# MCU_ESP32.net
KiCad netlist of a schematic drawn in Altium Designer
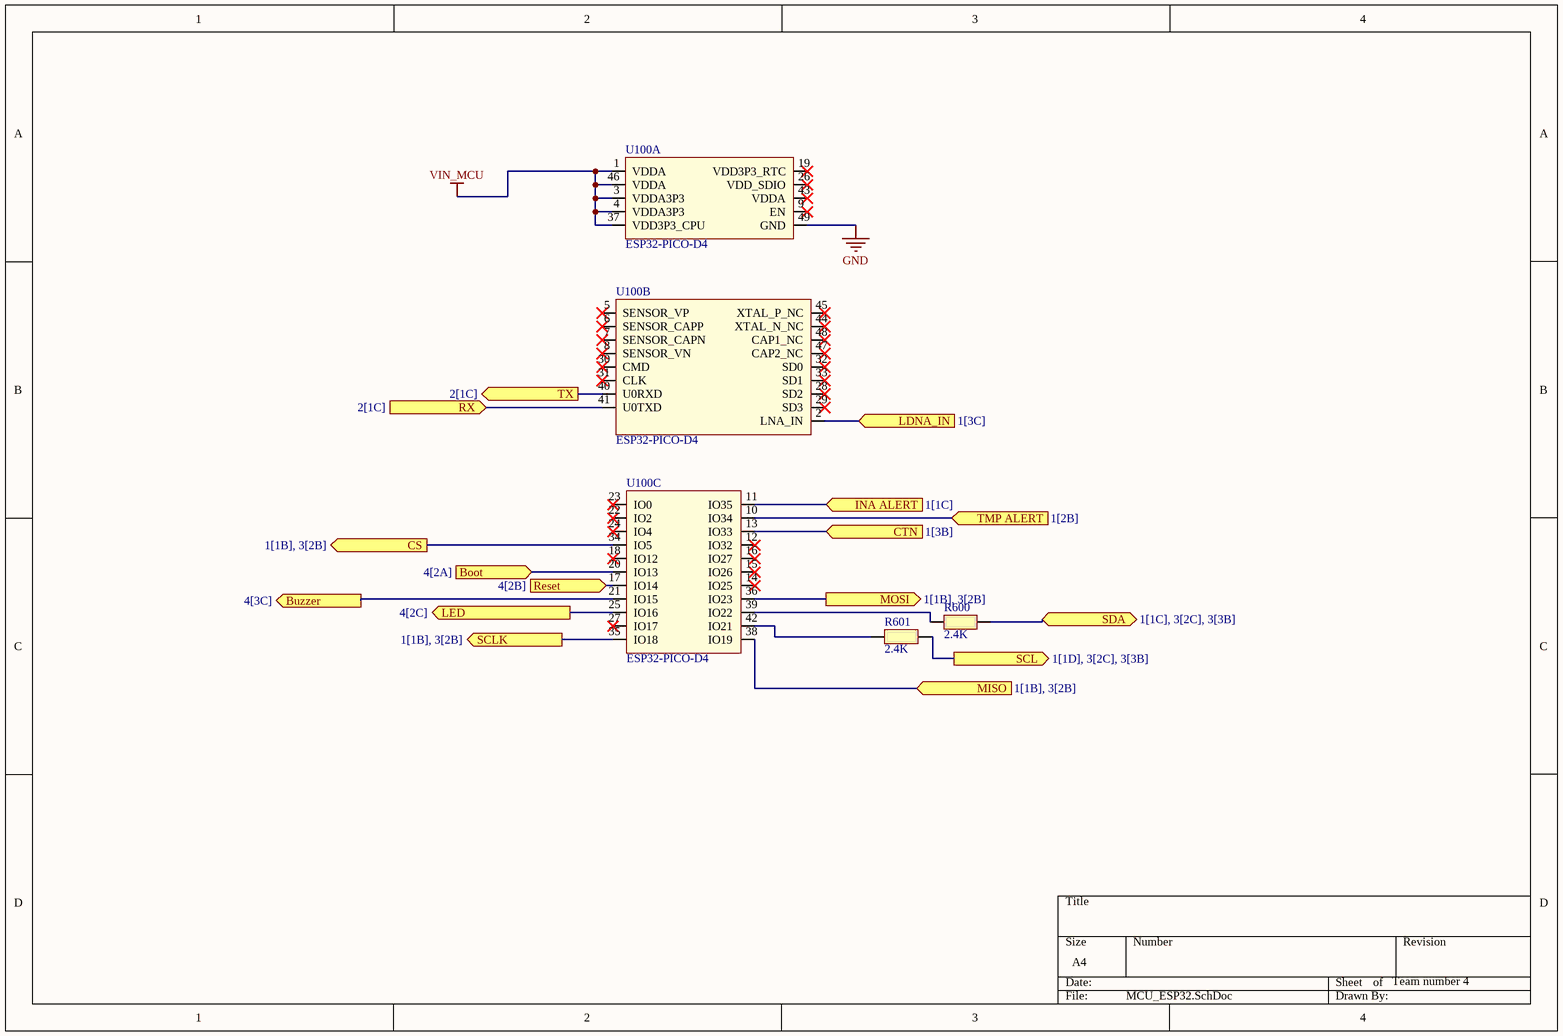
[diagram p0: MCU_ESP32.SchDoc]

(export (version "E")
  (design (tool "Eeschema 10.0.6"))
  (components
    (comp (ref "R600")
      (value "2.4K")
      (footprint "RESC1005X06N")
      (libsource (lib "SCHLibrary") (part "Resistor"))
    )
    (comp (ref "R601")
      (value "2.4K")
      (footprint "RESC1005X06N")
      (libsource (lib "SCHLibrary") (part "Resistor"))
    )
    (comp (ref "U100")
      (value "ESP32-PICO-D4")
      (footprint "PQFN50P700X700X104_HS-49N")
      (libsource (lib "SCHLibrary") (part "ESP32"))
    )
  )
  (nets
    (net (code "1") (name "/Boot") (class "Default")
      (node (ref "U100") (pin "20") (pinfunction "IO13_20") (pintype "passive"))
    )
    (net (code "2") (name "/Buzzer") (class "Default")
      (node (ref "U100") (pin "21") (pinfunction "IO15_21") (pintype "passive"))
    )
    (net (code "3") (name "/CS") (class "Default")
      (node (ref "U100") (pin "34") (pinfunction "IO5_34") (pintype "passive"))
    )
    (net (code "4") (name "/CTN") (class "Default")
      (node (ref "U100") (pin "13") (pinfunction "IO33_13") (pintype "passive"))
    )
    (net (code "5") (name "/INA ALERT") (class "Default")
      (node (ref "U100") (pin "11") (pinfunction "IO35_11") (pintype "passive"))
    )
    (net (code "6") (name "/LDNA_IN") (class "Default")
      (node (ref "U100") (pin "2") (pinfunction "LNA_IN_2") (pintype "passive"))
    )
    (net (code "7") (name "/LED") (class "Default")
      (node (ref "U100") (pin "25") (pinfunction "IO16_25") (pintype "passive"))
    )
    (net (code "8") (name "/MISO") (class "Default")
      (node (ref "U100") (pin "38") (pinfunction "IO19_38") (pintype "passive"))
    )
    (net (code "9") (name "/MOSI") (class "Default")
      (node (ref "U100") (pin "36") (pinfunction "IO23_36") (pintype "passive"))
    )
    (net (code "10") (name "/RX") (class "Default")
      (node (ref "U100") (pin "41") (pinfunction "U0TXD_41") (pintype "passive"))
    )
    (net (code "11") (name "/Reset") (class "Default")
      (node (ref "U100") (pin "17") (pinfunction "IO14_17") (pintype "passive"))
    )
    (net (code "12") (name "/SCL") (class "Default")
      (node (ref "R601") (pin "2") (pinfunction "2_2") (pintype "passive"))
    )
    (net (code "13") (name "/SCLK") (class "Default")
      (node (ref "U100") (pin "35") (pinfunction "IO18_35") (pintype "passive"))
    )
    (net (code "14") (name "/SDA") (class "Default")
      (node (ref "R600") (pin "2") (pinfunction "2_2") (pintype "passive"))
    )
    (net (code "15") (name "/TMP ALERT") (class "Default")
      (node (ref "U100") (pin "10") (pinfunction "IO34_10") (pintype "passive"))
    )
    (net (code "16") (name "/TX") (class "Default")
      (node (ref "U100") (pin "40") (pinfunction "U0RXD_40") (pintype "passive"))
    )
    (net (code "17") (name "GND") (class "Default")
      (node (ref "U100") (pin "49") (pinfunction "GND_49") (pintype "passive"))
    )
    (net (code "18") (name "Net-(U100C-IO21)") (class "Default")
      (node (ref "R601") (pin "1") (pinfunction "1_1") (pintype "passive"))
      (node (ref "U100") (pin "42") (pinfunction "IO21_42") (pintype "passive"))
    )
    (net (code "19") (name "Net-(U100C-IO22)") (class "Default")
      (node (ref "R600") (pin "1") (pinfunction "1_1") (pintype "passive"))
      (node (ref "U100") (pin "39") (pinfunction "IO22_39") (pintype "passive"))
    )
    (net (code "20") (name "VIN_MCU") (class "Default")
      (node (ref "U100") (pin "1") (pinfunction "VDDA_1") (pintype "passive"))
      (node (ref "U100") (pin "3") (pinfunction "VDDA3P3_3") (pintype "passive"))
      (node (ref "U100") (pin "37") (pinfunction "VDD3P3_CPU_37") (pintype "passive"))
      (node (ref "U100") (pin "4") (pinfunction "VDDA3P3_4") (pintype "passive"))
      (node (ref "U100") (pin "46") (pinfunction "VDDA_46") (pintype "passive"))
    )
    (net (code "21") (name "unconnected-(U100A-EN-Pad9)") (class "Default")
      (node (ref "U100") (pin "9") (pinfunction "EN_9") (pintype "passive+no_connect"))
    )
    (net (code "22") (name "unconnected-(U100A-VDD3P3_RTC-Pad19)") (class "Default")
      (node (ref "U100") (pin "19") (pinfunction "VDD3P3_RTC_19") (pintype "passive+no_connect"))
    )
    (net (code "23") (name "unconnected-(U100A-VDDA-Pad43)") (class "Default")
      (node (ref "U100") (pin "43") (pinfunction "VDDA_43") (pintype "passive+no_connect"))
    )
    (net (code "24") (name "unconnected-(U100A-VDD_SDIO-Pad26)") (class "Default")
      (node (ref "U100") (pin "26") (pinfunction "VDD_SDIO_26") (pintype "passive+no_connect"))
    )
    (net (code "25") (name "unconnected-(U100B-CAP1_NC-Pad48)") (class "Default")
      (node (ref "U100") (pin "48") (pinfunction "CAP1_NC_48") (pintype "passive+no_connect"))
    )
    (net (code "26") (name "unconnected-(U100B-CAP2_NC-Pad47)") (class "Default")
      (node (ref "U100") (pin "47") (pinfunction "CAP2_NC_47") (pintype "passive+no_connect"))
    )
    (net (code "27") (name "unconnected-(U100B-CLK-Pad31)") (class "Default")
      (node (ref "U100") (pin "31") (pinfunction "CLK_31") (pintype "passive+no_connect"))
    )
    (net (code "28") (name "unconnected-(U100B-CMD-Pad30)") (class "Default")
      (node (ref "U100") (pin "30") (pinfunction "CMD_30") (pintype "passive+no_connect"))
    )
    (net (code "29") (name "unconnected-(U100B-SD0-Pad32)") (class "Default")
      (node (ref "U100") (pin "32") (pinfunction "SD0_32") (pintype "passive+no_connect"))
    )
    (net (code "30") (name "unconnected-(U100B-SD1-Pad33)") (class "Default")
      (node (ref "U100") (pin "33") (pinfunction "SD1_33") (pintype "passive+no_connect"))
    )
    (net (code "31") (name "unconnected-(U100B-SD2-Pad28)") (class "Default")
      (node (ref "U100") (pin "28") (pinfunction "SD2_28") (pintype "passive+no_connect"))
    )
    (net (code "32") (name "unconnected-(U100B-SD3-Pad29)") (class "Default")
      (node (ref "U100") (pin "29") (pinfunction "SD3_29") (pintype "passive+no_connect"))
    )
    (net (code "33") (name "unconnected-(U100B-SENSOR_CAPN-Pad7)") (class "Default")
      (node (ref "U100") (pin "7") (pinfunction "SENSOR_CAPN_7") (pintype "passive+no_connect"))
    )
    (net (code "34") (name "unconnected-(U100B-SENSOR_CAPP-Pad6)") (class "Default")
      (node (ref "U100") (pin "6") (pinfunction "SENSOR_CAPP_6") (pintype "passive+no_connect"))
    )
    (net (code "35") (name "unconnected-(U100B-SENSOR_VN-Pad8)") (class "Default")
      (node (ref "U100") (pin "8") (pinfunction "SENSOR_VN_8") (pintype "passive+no_connect"))
    )
    (net (code "36") (name "unconnected-(U100B-SENSOR_VP-Pad5)") (class "Default")
      (node (ref "U100") (pin "5") (pinfunction "SENSOR_VP_5") (pintype "passive+no_connect"))
    )
    (net (code "37") (name "unconnected-(U100B-XTAL_N_NC-Pad44)") (class "Default")
      (node (ref "U100") (pin "44") (pinfunction "XTAL_N_NC_44") (pintype "passive+no_connect"))
    )
    (net (code "38") (name "unconnected-(U100B-XTAL_P_NC-Pad45)") (class "Default")
      (node (ref "U100") (pin "45") (pinfunction "XTAL_P_NC_45") (pintype "passive+no_connect"))
    )
    (net (code "39") (name "unconnected-(U100C-IO0-Pad23)") (class "Default")
      (node (ref "U100") (pin "23") (pinfunction "IO0_23") (pintype "passive+no_connect"))
    )
    (net (code "40") (name "unconnected-(U100C-IO2-Pad22)") (class "Default")
      (node (ref "U100") (pin "22") (pinfunction "IO2_22") (pintype "passive+no_connect"))
    )
    (net (code "41") (name "unconnected-(U100C-IO4-Pad24)") (class "Default")
      (node (ref "U100") (pin "24") (pinfunction "IO4_24") (pintype "passive+no_connect"))
    )
    (net (code "42") (name "unconnected-(U100C-IO12-Pad18)") (class "Default")
      (node (ref "U100") (pin "18") (pinfunction "IO12_18") (pintype "passive+no_connect"))
    )
    (net (code "43") (name "unconnected-(U100C-IO17-Pad27)") (class "Default")
      (node (ref "U100") (pin "27") (pinfunction "IO17_27") (pintype "passive+no_connect"))
    )
    (net (code "44") (name "unconnected-(U100C-IO25-Pad14)") (class "Default")
      (node (ref "U100") (pin "14") (pinfunction "IO25_14") (pintype "passive+no_connect"))
    )
    (net (code "45") (name "unconnected-(U100C-IO26-Pad15)") (class "Default")
      (node (ref "U100") (pin "15") (pinfunction "IO26_15") (pintype "passive+no_connect"))
    )
    (net (code "46") (name "unconnected-(U100C-IO27-Pad16)") (class "Default")
      (node (ref "U100") (pin "16") (pinfunction "IO27_16") (pintype "passive+no_connect"))
    )
    (net (code "47") (name "unconnected-(U100C-IO32-Pad12)") (class "Default")
      (node (ref "U100") (pin "12") (pinfunction "IO32_12") (pintype "passive+no_connect"))
    )
  )
)
